# Box.net
KiCad netlist of a schematic drawn in Altium Designer
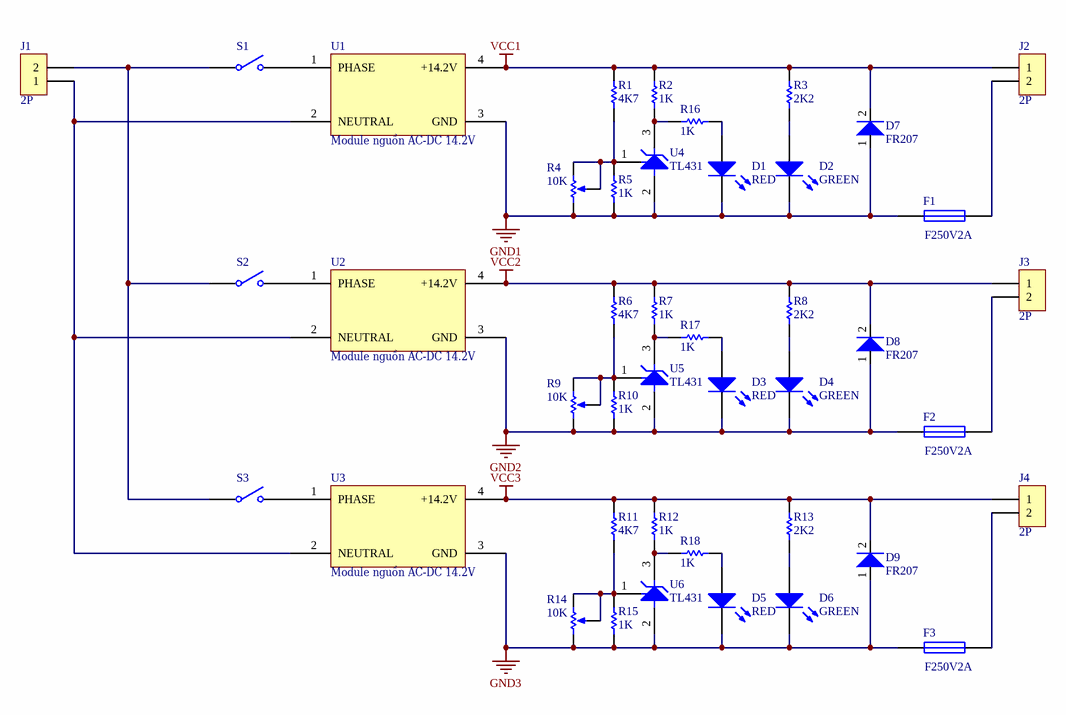
[diagram p0: Box.SchDoc]

(export (version "E")
  (design (tool "Eeschema 10.0.6"))
  (components
    (comp (ref "D1")
      (value "RED")
      (footprint "LED-0")
      (description "Typical INFRARED GaAs LED")
      (fields (field (name "Comment") "LED chân cắm 5mmRED") (field (name "PUBLISHER") "*"))
      (libsource (lib "DnsSchLib") (part "LED0"))
    )
    (comp (ref "D2")
      (value "GREEN")
      (footprint "LED-0")
      (description "Typical INFRARED GaAs LED")
      (fields (field (name "Comment") "LED chân cắm 5mmGREEN") (field (name "PUBLISHER") "*"))
      (libsource (lib "DnsSchLib") (part "LED0"))
    )
    (comp (ref "D3")
      (value "RED")
      (footprint "LED-0")
      (description "Typical INFRARED GaAs LED")
      (fields (field (name "Comment") "LED chân cắm 5mmRED") (field (name "PUBLISHER") "*"))
      (libsource (lib "DnsSchLib") (part "LED0"))
    )
    (comp (ref "D4")
      (value "GREEN")
      (footprint "LED-0")
      (description "Typical INFRARED GaAs LED")
      (fields (field (name "Comment") "LED chân cắm 5mmGREEN") (field (name "PUBLISHER") "*"))
      (libsource (lib "DnsSchLib") (part "LED0"))
    )
    (comp (ref "D5")
      (value "RED")
      (footprint "LED-0")
      (description "Typical INFRARED GaAs LED")
      (fields (field (name "Comment") "LED chân cắm 5mmRED") (field (name "PUBLISHER") "*"))
      (libsource (lib "DnsSchLib") (part "LED0"))
    )
    (comp (ref "D6")
      (value "GREEN")
      (footprint "LED-0")
      (description "Typical INFRARED GaAs LED")
      (fields (field (name "Comment") "LED chân cắm 5mmGREEN") (field (name "PUBLISHER") "*"))
      (libsource (lib "DnsSchLib") (part "LED0"))
    )
    (comp (ref "D7")
      (value "FR207")
      (footprint "DIODE1A")
      (fields (field (name "Comment") "Diode xung chân cắm 2AFR207"))
      (libsource (lib "DnsSchLib") (part "DIODE"))
    )
    (comp (ref "D8")
      (value "FR207")
      (footprint "DIODE1A")
      (fields (field (name "Comment") "Diode xung chân cắm 2AFR207"))
      (libsource (lib "DnsSchLib") (part "DIODE"))
    )
    (comp (ref "D9")
      (value "FR207")
      (footprint "DIODE1A")
      (fields (field (name "Comment") "Diode xung chân cắm 2AFR207"))
      (libsource (lib "DnsSchLib") (part "DIODE"))
    )
    (comp (ref "F1")
      (value "F250V2A")
      (footprint "FUSE2")
      (description "Fuse")
      (fields
        (field (name "Comment") "Cầu chì và đế cầu chìF250V2A")
        (field (name "PUBLISHER") "Altium Limited")
      )
      (libsource (lib "Miscellaneous Devices") (part "Fuse 1"))
    )
    (comp (ref "F2")
      (value "F250V2A")
      (footprint "FUSE2")
      (description "Fuse")
      (fields
        (field (name "Comment") "Cầu chì và đế cầu chìF250V2A")
        (field (name "PUBLISHER") "Altium Limited")
      )
      (libsource (lib "Miscellaneous Devices") (part "Fuse 1"))
    )
    (comp (ref "F3")
      (value "F250V2A")
      (footprint "FUSE2")
      (description "Fuse")
      (fields
        (field (name "Comment") "Cầu chì và đế cầu chìF250V2A")
        (field (name "PUBLISHER") "Altium Limited")
      )
      (libsource (lib "Miscellaneous Devices") (part "Fuse 1"))
    )
    (comp (ref "J1")
      (value "2P")
      (footprint "JACK2")
      (fields (field (name "Comment") "Giắc xanh loại đứng, 300V/16A - 5.08mm 2P"))
      (libsource (lib "DnsSchLib") (part "CON2"))
    )
    (comp (ref "J2")
      (value "2P")
      (footprint "JACK2")
      (fields (field (name "Comment") "Giắc xanh loại đứng, 300V/16A - 5.08mm 2P"))
      (libsource (lib "") (part "CON2_1"))
    )
    (comp (ref "J3")
      (value "2P")
      (footprint "JACK2")
      (fields (field (name "Comment") "Giắc xanh loại đứng, 300V/16A - 5.08mm 2P"))
      (libsource (lib "") (part "CON2_1"))
    )
    (comp (ref "J4")
      (value "2P")
      (footprint "JACK2")
      (fields (field (name "Comment") "Giắc xanh loại đứng, 300V/16A - 5.08mm 2P"))
      (libsource (lib "") (part "CON2_1"))
    )
    (comp (ref "R1")
      (value "4K7")
      (footprint "0805DD")
      (description "Semiconductor Resistor")
      (fields (field (name "Comment") "Điện trở dán 08054K7") (field (name "PUBLISHER") "*"))
      (libsource (lib "DnsSchLib") (part "Res Semi"))
    )
    (comp (ref "R2")
      (value "1K")
      (footprint "0805DD")
      (description "Semiconductor Resistor")
      (fields (field (name "Comment") "Điện trở dán 08051K") (field (name "PUBLISHER") "*"))
      (libsource (lib "DnsSchLib") (part "Res Semi"))
    )
    (comp (ref "R3")
      (value "2K2")
      (footprint "0805DD")
      (description "Semiconductor Resistor")
      (fields (field (name "Comment") "Điện trở dán 08052K2") (field (name "PUBLISHER") "*"))
      (libsource (lib "DnsSchLib") (part "Res Semi"))
    )
    (comp (ref "R4")
      (value "10K")
      (footprint "BTXANH")
      (description "Potentiometer")
      (fields (field (name "Comment") "Biến trở vi chỉnh TRIMMER 329610K") (field (name "PUBLISHER") "*"))
      (libsource (lib "DnsSchLib") (part "RPot"))
    )
    (comp (ref "R5")
      (value "1K")
      (footprint "0805DD")
      (description "Semiconductor Resistor")
      (fields (field (name "Comment") "Điện trở dán 08051K") (field (name "PUBLISHER") "*"))
      (libsource (lib "DnsSchLib") (part "Res Semi"))
    )
    (comp (ref "R6")
      (value "4K7")
      (footprint "0805DD")
      (description "Semiconductor Resistor")
      (fields (field (name "Comment") "Điện trở dán 08054K7") (field (name "PUBLISHER") "*"))
      (libsource (lib "DnsSchLib") (part "Res Semi"))
    )
    (comp (ref "R7")
      (value "1K")
      (footprint "0805DD")
      (description "Semiconductor Resistor")
      (fields (field (name "Comment") "Điện trở dán 08051K") (field (name "PUBLISHER") "*"))
      (libsource (lib "DnsSchLib") (part "Res Semi"))
    )
    (comp (ref "R8")
      (value "2K2")
      (footprint "0805DD")
      (description "Semiconductor Resistor")
      (fields (field (name "Comment") "Điện trở dán 08052K2") (field (name "PUBLISHER") "*"))
      (libsource (lib "DnsSchLib") (part "Res Semi"))
    )
    (comp (ref "R9")
      (value "10K")
      (footprint "BTXANH")
      (description "Potentiometer")
      (fields (field (name "Comment") "Biến trở vi chỉnh TRIMMER 329610K") (field (name "PUBLISHER") "*"))
      (libsource (lib "DnsSchLib") (part "RPot"))
    )
    (comp (ref "R10")
      (value "1K")
      (footprint "0805DD")
      (description "Semiconductor Resistor")
      (fields (field (name "Comment") "Điện trở dán 08051K") (field (name "PUBLISHER") "*"))
      (libsource (lib "DnsSchLib") (part "Res Semi"))
    )
    (comp (ref "R11")
      (value "4K7")
      (footprint "0805DD")
      (description "Semiconductor Resistor")
      (fields (field (name "Comment") "Điện trở dán 08054K7") (field (name "PUBLISHER") "*"))
      (libsource (lib "DnsSchLib") (part "Res Semi"))
    )
    (comp (ref "R12")
      (value "1K")
      (footprint "0805DD")
      (description "Semiconductor Resistor")
      (fields (field (name "Comment") "Điện trở dán 08051K") (field (name "PUBLISHER") "*"))
      (libsource (lib "DnsSchLib") (part "Res Semi"))
    )
    (comp (ref "R13")
      (value "2K2")
      (footprint "0805DD")
      (description "Semiconductor Resistor")
      (fields (field (name "Comment") "Điện trở dán 08052K2") (field (name "PUBLISHER") "*"))
      (libsource (lib "DnsSchLib") (part "Res Semi"))
    )
    (comp (ref "R14")
      (value "10K")
      (footprint "BTXANH")
      (description "Potentiometer")
      (fields (field (name "Comment") "Biến trở vi chỉnh TRIMMER 329610K") (field (name "PUBLISHER") "*"))
      (libsource (lib "DnsSchLib") (part "RPot"))
    )
    (comp (ref "R15")
      (value "1K")
      (footprint "0805DD")
      (description "Semiconductor Resistor")
      (fields (field (name "Comment") "Điện trở dán 08051K") (field (name "PUBLISHER") "*"))
      (libsource (lib "DnsSchLib") (part "Res Semi"))
    )
    (comp (ref "R16")
      (value "1K")
      (footprint "0805DD")
      (description "Semiconductor Resistor")
      (fields (field (name "Comment") "Điện trở dán 08051K") (field (name "PUBLISHER") "*"))
      (libsource (lib "DnsSchLib") (part "Res Semi"))
    )
    (comp (ref "R17")
      (value "1K")
      (footprint "0805DD")
      (description "Semiconductor Resistor")
      (fields (field (name "Comment") "Điện trở dán 08051K") (field (name "PUBLISHER") "*"))
      (libsource (lib "DnsSchLib") (part "Res Semi"))
    )
    (comp (ref "R18")
      (value "1K")
      (footprint "0805DD")
      (description "Semiconductor Resistor")
      (fields (field (name "Comment") "Điện trở dán 08051K") (field (name "PUBLISHER") "*"))
      (libsource (lib "DnsSchLib") (part "Res Semi"))
    )
    (comp (ref "S1")
      (value "Giắc cắm loại đứng, 300V/16A - 5.08mm 2P")
      (footprint "JACK2")
      (description "Single-Pole, Single-Throw Switch")
      (fields (field (name "PUBLISHER") "Altium Limited"))
      (libsource (lib "Miscellaneous Devices") (part "SW-SPST"))
    )
    (comp (ref "S2")
      (value "Giắc cắm loại đứng, 300V/16A - 5.08mm 2P")
      (footprint "JACK2")
      (description "Single-Pole, Single-Throw Switch")
      (fields (field (name "PUBLISHER") "Altium Limited"))
      (libsource (lib "Miscellaneous Devices") (part "SW-SPST"))
    )
    (comp (ref "S3")
      (value "Giắc cắm loại đứng, 300V/16A - 5.08mm 2P")
      (footprint "JACK2")
      (description "Single-Pole, Single-Throw Switch")
      (fields (field (name "PUBLISHER") "Altium Limited"))
      (libsource (lib "Miscellaneous Devices") (part "SW-SPST"))
    )
    (comp (ref "U1")
      (value "Module nguồn AC-DC 14.2V")
      (footprint "PS15V2A")
      (libsource (lib "DnsSchLib") (part "SACACQUY"))
    )
    (comp (ref "U2")
      (value "Module nguồn AC-DC 14.2V")
      (footprint "PS15V2A")
      (libsource (lib "DnsSchLib") (part "SACACQUY"))
    )
    (comp (ref "U3")
      (value "Module nguồn AC-DC 14.2V")
      (footprint "PS15V2A")
      (libsource (lib "DnsSchLib") (part "SACACQUY"))
    )
    (comp (ref "U4")
      (value "TL431")
      (footprint "TO92_431")
      (description "Adjustable Precision Shunt Regulator")
      (fields (field (name "Comment") "IC điện áp chuẩn, chân cắm TO92TL431"))
      (libsource (lib "DnsSchLib") (part "TL431"))
    )
    (comp (ref "U5")
      (value "TL431")
      (footprint "TO92_431")
      (description "Adjustable Precision Shunt Regulator")
      (fields (field (name "Comment") "IC điện áp chuẩn, chân cắm TO92TL431"))
      (libsource (lib "DnsSchLib") (part "TL431"))
    )
    (comp (ref "U6")
      (value "TL431")
      (footprint "TO92_431")
      (description "Adjustable Precision Shunt Regulator")
      (fields (field (name "Comment") "IC điện áp chuẩn, chân cắm TO92TL431"))
      (libsource (lib "DnsSchLib") (part "TL431"))
    )
  )
  (nets
    (net (code "1") (name "GND1") (class "Default")
      (node (ref "D1") (pin "2") (pinfunction "K_2") (pintype "passive"))
      (node (ref "D2") (pin "2") (pinfunction "K_2") (pintype "passive"))
      (node (ref "D7") (pin "1") (pinfunction "A_1") (pintype "passive"))
      (node (ref "F1") (pin "1") (pinfunction "1_1") (pintype "passive"))
      (node (ref "R4") (pin "1") (pinfunction "TOP_1") (pintype "passive"))
      (node (ref "R5") (pin "1") (pinfunction "1_1") (pintype "passive"))
      (node (ref "U1") (pin "3") (pinfunction "GND_3") (pintype "passive"))
      (node (ref "U4") (pin "2") (pinfunction "A_2") (pintype "passive"))
    )
    (net (code "2") (name "GND2") (class "Default")
      (node (ref "D3") (pin "2") (pinfunction "K_2") (pintype "passive"))
      (node (ref "D4") (pin "2") (pinfunction "K_2") (pintype "passive"))
      (node (ref "D8") (pin "1") (pinfunction "A_1") (pintype "passive"))
      (node (ref "F2") (pin "1") (pinfunction "1_1") (pintype "passive"))
      (node (ref "R10") (pin "1") (pinfunction "1_1") (pintype "passive"))
      (node (ref "R9") (pin "1") (pinfunction "TOP_1") (pintype "passive"))
      (node (ref "U2") (pin "3") (pinfunction "GND_3") (pintype "passive"))
      (node (ref "U5") (pin "2") (pinfunction "A_2") (pintype "passive"))
    )
    (net (code "3") (name "GND3") (class "Default")
      (node (ref "D5") (pin "2") (pinfunction "K_2") (pintype "passive"))
      (node (ref "D6") (pin "2") (pinfunction "K_2") (pintype "passive"))
      (node (ref "D9") (pin "1") (pinfunction "A_1") (pintype "passive"))
      (node (ref "F3") (pin "1") (pinfunction "1_1") (pintype "passive"))
      (node (ref "R14") (pin "1") (pinfunction "TOP_1") (pintype "passive"))
      (node (ref "R15") (pin "1") (pinfunction "1_1") (pintype "passive"))
      (node (ref "U3") (pin "3") (pinfunction "GND_3") (pintype "passive"))
      (node (ref "U6") (pin "2") (pinfunction "A_2") (pintype "passive"))
    )
    (net (code "4") (name "Net-(D1-A)") (class "Default")
      (node (ref "D1") (pin "1") (pinfunction "A_1") (pintype "passive"))
      (node (ref "R16") (pin "1") (pinfunction "1_1") (pintype "passive"))
    )
    (net (code "5") (name "Net-(D2-A)") (class "Default")
      (node (ref "D2") (pin "1") (pinfunction "A_1") (pintype "passive"))
      (node (ref "R3") (pin "1") (pinfunction "1_1") (pintype "passive"))
    )
    (net (code "6") (name "Net-(D3-A)") (class "Default")
      (node (ref "D3") (pin "1") (pinfunction "A_1") (pintype "passive"))
      (node (ref "R17") (pin "1") (pinfunction "1_1") (pintype "passive"))
    )
    (net (code "7") (name "Net-(D4-A)") (class "Default")
      (node (ref "D4") (pin "1") (pinfunction "A_1") (pintype "passive"))
      (node (ref "R8") (pin "1") (pinfunction "1_1") (pintype "passive"))
    )
    (net (code "8") (name "Net-(D5-A)") (class "Default")
      (node (ref "D5") (pin "1") (pinfunction "A_1") (pintype "passive"))
      (node (ref "R18") (pin "1") (pinfunction "1_1") (pintype "passive"))
    )
    (net (code "9") (name "Net-(D6-A)") (class "Default")
      (node (ref "D6") (pin "1") (pinfunction "A_1") (pintype "passive"))
      (node (ref "R13") (pin "1") (pinfunction "1_1") (pintype "passive"))
    )
    (net (code "10") (name "Net-(F1-Pad2)") (class "Default")
      (node (ref "F1") (pin "2") (pinfunction "2_2") (pintype "passive"))
      (node (ref "J2") (pin "2") (pinfunction "2_2") (pintype "passive"))
    )
    (net (code "11") (name "Net-(F2-Pad2)") (class "Default")
      (node (ref "F2") (pin "2") (pinfunction "2_2") (pintype "passive"))
      (node (ref "J3") (pin "2") (pinfunction "2_2") (pintype "passive"))
    )
    (net (code "12") (name "Net-(F3-Pad2)") (class "Default")
      (node (ref "F3") (pin "2") (pinfunction "2_2") (pintype "passive"))
      (node (ref "J4") (pin "2") (pinfunction "2_2") (pintype "passive"))
    )
    (net (code "13") (name "Net-(R4-BOT)") (class "Default")
      (node (ref "R1") (pin "2") (pinfunction "2_2") (pintype "passive"))
      (node (ref "R4") (pin "2") (pinfunction "TAP_2") (pintype "passive"))
      (node (ref "R4") (pin "3") (pinfunction "BOT_3") (pintype "passive"))
      (node (ref "R5") (pin "2") (pinfunction "2_2") (pintype "passive"))
      (node (ref "U4") (pin "1") (pinfunction "R_1") (pintype "passive"))
    )
    (net (code "14") (name "Net-(R9-BOT)") (class "Default")
      (node (ref "R10") (pin "2") (pinfunction "2_2") (pintype "passive"))
      (node (ref "R6") (pin "2") (pinfunction "2_2") (pintype "passive"))
      (node (ref "R9") (pin "2") (pinfunction "TAP_2") (pintype "passive"))
      (node (ref "R9") (pin "3") (pinfunction "BOT_3") (pintype "passive"))
      (node (ref "U5") (pin "1") (pinfunction "R_1") (pintype "passive"))
    )
    (net (code "15") (name "Net-(R14-BOT)") (class "Default")
      (node (ref "R11") (pin "2") (pinfunction "2_2") (pintype "passive"))
      (node (ref "R14") (pin "2") (pinfunction "TAP_2") (pintype "passive"))
      (node (ref "R14") (pin "3") (pinfunction "BOT_3") (pintype "passive"))
      (node (ref "R15") (pin "2") (pinfunction "2_2") (pintype "passive"))
      (node (ref "U6") (pin "1") (pinfunction "R_1") (pintype "passive"))
    )
    (net (code "16") (name "Net-(S1-COMMON)") (class "Default")
      (node (ref "J1") (pin "2") (pinfunction "2_2") (pintype "passive"))
      (node (ref "S1") (pin "1") (pinfunction "COMMON_1") (pintype "passive"))
      (node (ref "S2") (pin "1") (pinfunction "COMMON_1") (pintype "passive"))
      (node (ref "S3") (pin "1") (pinfunction "COMMON_1") (pintype "passive"))
    )
    (net (code "17") (name "Net-(S1-NO)") (class "Default")
      (node (ref "S1") (pin "2") (pinfunction "NO_2") (pintype "passive"))
      (node (ref "U1") (pin "1") (pinfunction "PHASE_1") (pintype "passive"))
    )
    (net (code "18") (name "Net-(S2-NO)") (class "Default")
      (node (ref "S2") (pin "2") (pinfunction "NO_2") (pintype "passive"))
      (node (ref "U2") (pin "1") (pinfunction "PHASE_1") (pintype "passive"))
    )
    (net (code "19") (name "Net-(S3-NO)") (class "Default")
      (node (ref "S3") (pin "2") (pinfunction "NO_2") (pintype "passive"))
      (node (ref "U3") (pin "1") (pinfunction "PHASE_1") (pintype "passive"))
    )
    (net (code "20") (name "Net-(U1-NEUTRAL)") (class "Default")
      (node (ref "J1") (pin "1") (pinfunction "1_1") (pintype "passive"))
      (node (ref "U1") (pin "2") (pinfunction "NEUTRAL_2") (pintype "passive"))
      (node (ref "U2") (pin "2") (pinfunction "NEUTRAL_2") (pintype "passive"))
      (node (ref "U3") (pin "2") (pinfunction "NEUTRAL_2") (pintype "passive"))
    )
    (net (code "21") (name "Net-(U4-K)") (class "Default")
      (node (ref "R16") (pin "2") (pinfunction "2_2") (pintype "passive"))
      (node (ref "R2") (pin "1") (pinfunction "1_1") (pintype "passive"))
      (node (ref "U4") (pin "3") (pinfunction "K_3") (pintype "passive"))
    )
    (net (code "22") (name "Net-(U5-K)") (class "Default")
      (node (ref "R17") (pin "2") (pinfunction "2_2") (pintype "passive"))
      (node (ref "R7") (pin "1") (pinfunction "1_1") (pintype "passive"))
      (node (ref "U5") (pin "3") (pinfunction "K_3") (pintype "passive"))
    )
    (net (code "23") (name "Net-(U6-K)") (class "Default")
      (node (ref "R12") (pin "1") (pinfunction "1_1") (pintype "passive"))
      (node (ref "R18") (pin "2") (pinfunction "2_2") (pintype "passive"))
      (node (ref "U6") (pin "3") (pinfunction "K_3") (pintype "passive"))
    )
    (net (code "24") (name "VCC1") (class "Default")
      (node (ref "D7") (pin "2") (pinfunction "K_2") (pintype "passive"))
      (node (ref "J2") (pin "1") (pinfunction "1_1") (pintype "passive"))
      (node (ref "R1") (pin "1") (pinfunction "1_1") (pintype "passive"))
      (node (ref "R2") (pin "2") (pinfunction "2_2") (pintype "passive"))
      (node (ref "R3") (pin "2") (pinfunction "2_2") (pintype "passive"))
      (node (ref "U1") (pin "4") (pinfunction "+14.2V_4") (pintype "passive"))
    )
    (net (code "25") (name "VCC2") (class "Default")
      (node (ref "D8") (pin "2") (pinfunction "K_2") (pintype "passive"))
      (node (ref "J3") (pin "1") (pinfunction "1_1") (pintype "passive"))
      (node (ref "R6") (pin "1") (pinfunction "1_1") (pintype "passive"))
      (node (ref "R7") (pin "2") (pinfunction "2_2") (pintype "passive"))
      (node (ref "R8") (pin "2") (pinfunction "2_2") (pintype "passive"))
      (node (ref "U2") (pin "4") (pinfunction "+14.2V_4") (pintype "passive"))
    )
    (net (code "26") (name "VCC3") (class "Default")
      (node (ref "D9") (pin "2") (pinfunction "K_2") (pintype "passive"))
      (node (ref "J4") (pin "1") (pinfunction "1_1") (pintype "passive"))
      (node (ref "R11") (pin "1") (pinfunction "1_1") (pintype "passive"))
      (node (ref "R12") (pin "2") (pinfunction "2_2") (pintype "passive"))
      (node (ref "R13") (pin "2") (pinfunction "2_2") (pintype "passive"))
      (node (ref "U3") (pin "4") (pinfunction "+14.2V_4") (pintype "passive"))
    )
  )
)
